# SD_Card.net
KiCad netlist of a schematic drawn in Altium Designer
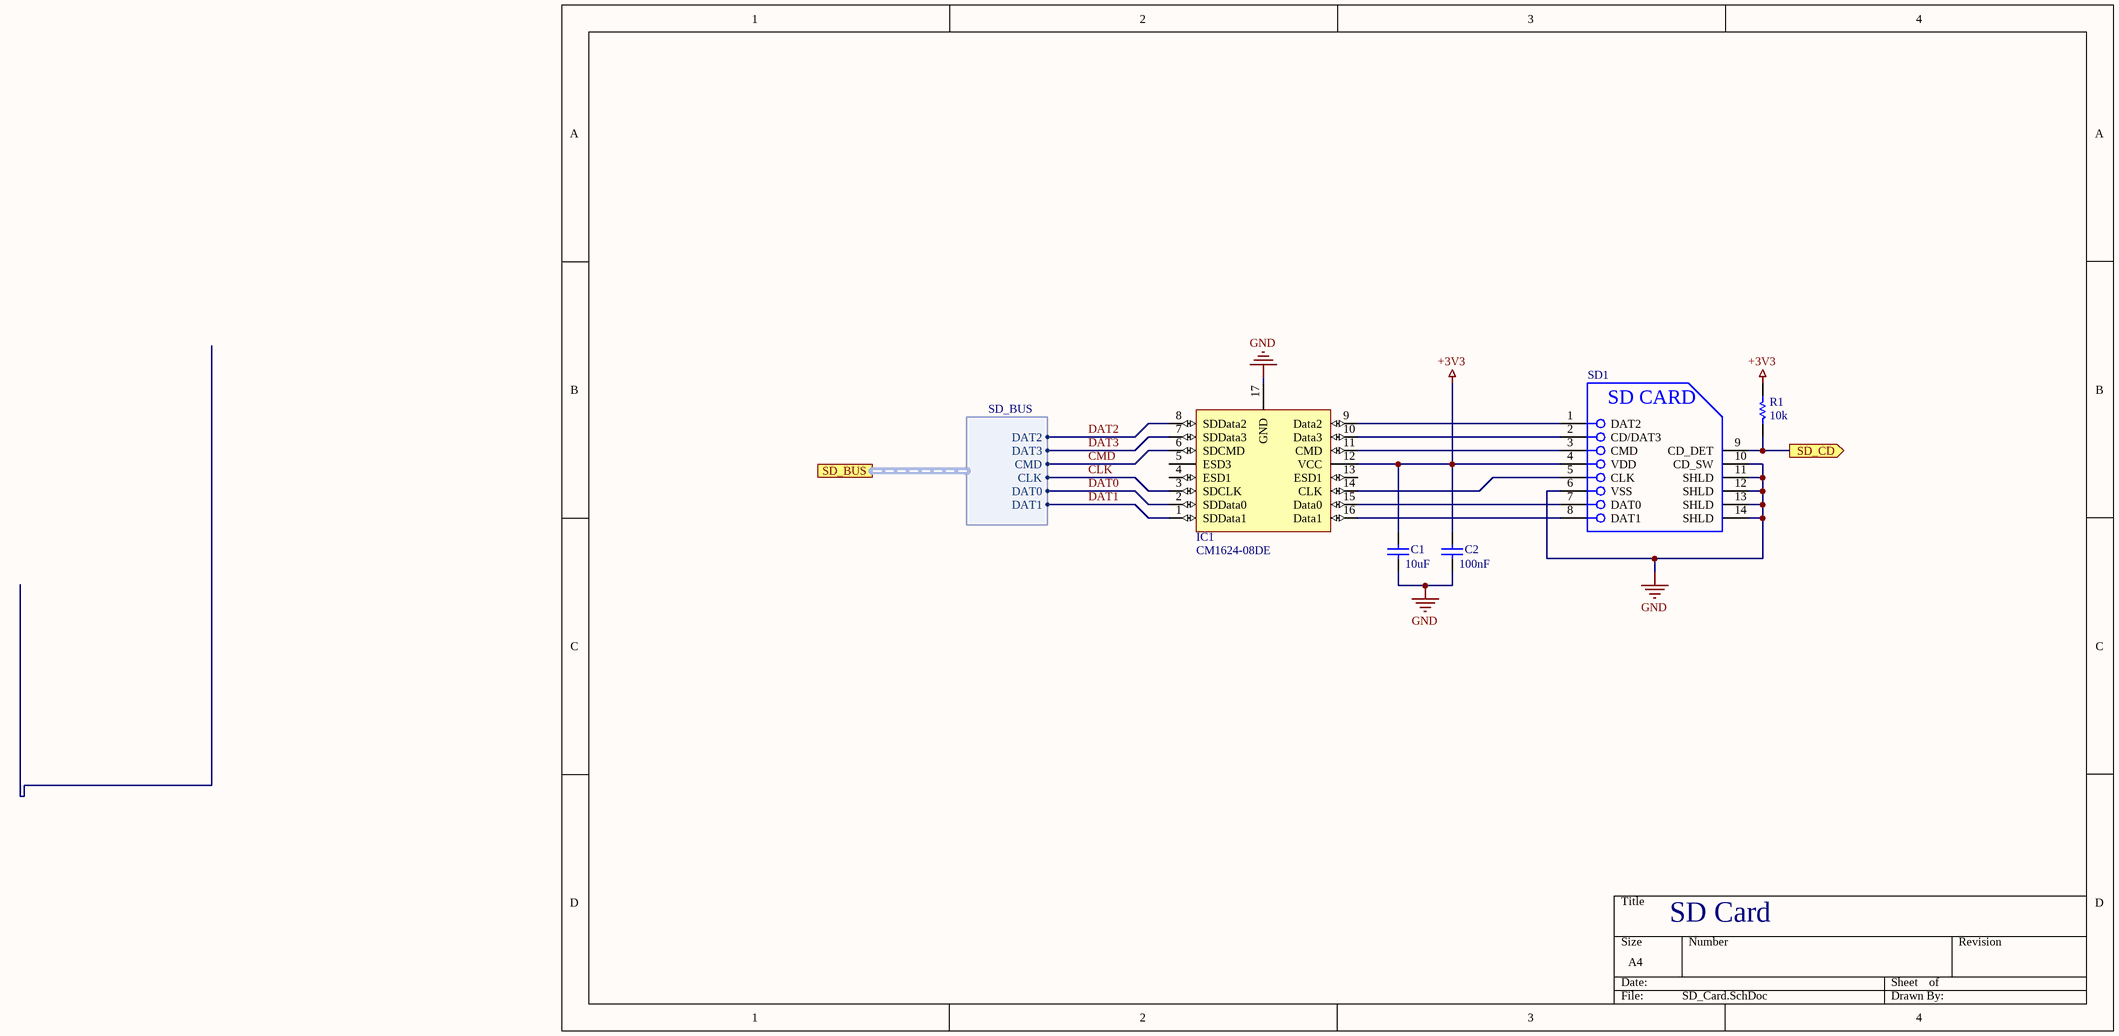
[diagram p0: SD_Card.SchDoc]

(export (version "E")
  (design (tool "Eeschema 10.0.6"))
  (components
    (comp (ref "C1")
      (value "10uF")
      (footprint "CAPC2012X14N")
      (description "CAP CER 10UF 10V X5R 0805")
      (fields (field (name "VOLTAGE") "10V") (field (name "TOLERANCE") "10%"))
      (libsource (lib "UWA Aerospace") (part "C0603C104M5RACTU"))
    )
    (comp (ref "C2")
      (value "100nF")
      (footprint "CAPC1608X10N")
      (description "Cap Ceramic 0.1uF 50V X7R 20% SMD 0603 125C T/R")
      (fields (field (name "TOLERANCE") "20%") (field (name "Comment") "C0603C104M5RACTU"))
      (libsource (lib "UWA Aerospace") (part "C0603C104M5RACTU"))
    )
    (comp (ref "IC1")
      (value "CM1624-08DE")
      (footprint "SON40P140X55_HS-17N")
      (description "EMI Filter Flat Style SMD T/R")
      (libsource (lib "UWA Aerospace") (part "CM1624-08DE"))
    )
    (comp (ref "R1")
      (value "10k")
      (footprint "RESC1608X06N")
      (fields (field (name "TOLERANCE") "1%") (field (name "Comment") "CRCW060310K0FKEA"))
      (libsource (lib "UWA Aerospace") (part "CRCW060310K0FKEA"))
    )
    (comp (ref "SD1")
      (value "5027740891")
      (footprint "5027740891-Footprint-1")
      (description "MOLEX   502774-0891.   MEMORY CARD CONNECTOR, MICROSD, 8POS")
      (libsource (lib "UWA Aerospace") (part "5027740891"))
    )
  )
  (nets
    (net (code "2") (name "+3V3") (class "Default")
      (node (ref "C1") (pin "2") (pinfunction "2_2") (pintype "passive"))
      (node (ref "C2") (pin "2") (pinfunction "2_2") (pintype "passive"))
      (node (ref "IC1") (pin "12") (pinfunction "VCC_12") (pintype "power_in"))
      (node (ref "R1") (pin "2") (pinfunction "2_2") (pintype "passive"))
      (node (ref "SD1") (pin "4") (pinfunction "VDD_4") (pintype "passive"))
    )
    (net (code "3") (name "/CLK") (class "Default")
      (node (ref "IC1") (pin "3") (pinfunction "SDCLK_3") (pintype "bidirectional"))
    )
    (net (code "4") (name "/CMD") (class "Default")
      (node (ref "IC1") (pin "6") (pinfunction "SDCMD_6") (pintype "bidirectional"))
    )
    (net (code "5") (name "/DAT0") (class "Default")
      (node (ref "IC1") (pin "2") (pinfunction "SDData0_2") (pintype "bidirectional"))
    )
    (net (code "6") (name "/DAT1") (class "Default")
      (node (ref "IC1") (pin "1") (pinfunction "SDData1_1") (pintype "bidirectional"))
    )
    (net (code "7") (name "/DAT2") (class "Default")
      (node (ref "IC1") (pin "8") (pinfunction "SDData2_8") (pintype "bidirectional"))
    )
    (net (code "8") (name "/DAT3") (class "Default")
      (node (ref "IC1") (pin "7") (pinfunction "SDData3_7") (pintype "bidirectional"))
    )
    (net (code "9") (name "/SD_CD") (class "Default")
      (node (ref "R1") (pin "1") (pinfunction "1_1") (pintype "passive"))
      (node (ref "SD1") (pin "9") (pinfunction "CD_DET_9") (pintype "passive"))
    )
    (net (code "11") (name "GND") (class "Default")
      (node (ref "C1") (pin "1") (pinfunction "1_1") (pintype "passive"))
      (node (ref "C2") (pin "1") (pinfunction "1_1") (pintype "passive"))
      (node (ref "IC1") (pin "17") (pinfunction "GND_17") (pintype "power_in"))
      (node (ref "SD1") (pin "10") (pinfunction "CD_SW_10") (pintype "passive"))
      (node (ref "SD1") (pin "11") (pinfunction "SHLD_11") (pintype "passive"))
      (node (ref "SD1") (pin "12") (pinfunction "SHLD_12") (pintype "passive"))
      (node (ref "SD1") (pin "13") (pinfunction "SHLD_13") (pintype "passive"))
      (node (ref "SD1") (pin "14") (pinfunction "SHLD_14") (pintype "passive"))
      (node (ref "SD1") (pin "6") (pinfunction "VSS_6") (pintype "passive"))
    )
    (net (code "12") (name "Net-(IC1-CLK)") (class "Default")
      (node (ref "IC1") (pin "14") (pinfunction "CLK_14") (pintype "bidirectional"))
      (node (ref "SD1") (pin "5") (pinfunction "CLK_5") (pintype "passive"))
    )
    (net (code "13") (name "Net-(IC1-CMD)") (class "Default")
      (node (ref "IC1") (pin "11") (pinfunction "CMD_11") (pintype "bidirectional"))
      (node (ref "SD1") (pin "3") (pinfunction "CMD_3") (pintype "passive"))
    )
    (net (code "14") (name "Net-(IC1-Data0)") (class "Default")
      (node (ref "IC1") (pin "15") (pinfunction "Data0_15") (pintype "bidirectional"))
      (node (ref "SD1") (pin "7") (pinfunction "DAT0_7") (pintype "passive"))
    )
    (net (code "15") (name "Net-(IC1-Data1)") (class "Default")
      (node (ref "IC1") (pin "16") (pinfunction "Data1_16") (pintype "bidirectional"))
      (node (ref "SD1") (pin "8") (pinfunction "DAT1_8") (pintype "passive"))
    )
    (net (code "16") (name "Net-(IC1-Data2)") (class "Default")
      (node (ref "IC1") (pin "9") (pinfunction "Data2_9") (pintype "bidirectional"))
      (node (ref "SD1") (pin "1") (pinfunction "DAT2_1") (pintype "passive"))
    )
    (net (code "17") (name "Net-(IC1-Data3)") (class "Default")
      (node (ref "IC1") (pin "10") (pinfunction "Data3_10") (pintype "bidirectional"))
      (node (ref "SD1") (pin "2") (pinfunction "CD/DAT3_2") (pintype "passive"))
    )
    (net (code "18") (name "unconnected-(IC1-ESD1-Pad4)") (class "Default")
      (node (ref "IC1") (pin "4") (pinfunction "ESD1_4") (pintype "bidirectional"))
    )
    (net (code "19") (name "unconnected-(IC1-ESD1-Pad13)") (class "Default")
      (node (ref "IC1") (pin "13") (pinfunction "ESD1_13") (pintype "bidirectional"))
    )
    (net (code "20") (name "unconnected-(IC1-ESD3-Pad5)") (class "Default")
      (node (ref "IC1") (pin "5") (pinfunction "ESD3_5") (pintype "passive"))
    )
  )
)
